# balancing_robot_psoc.net
KiCad netlist of a schematic drawn in EAGLE
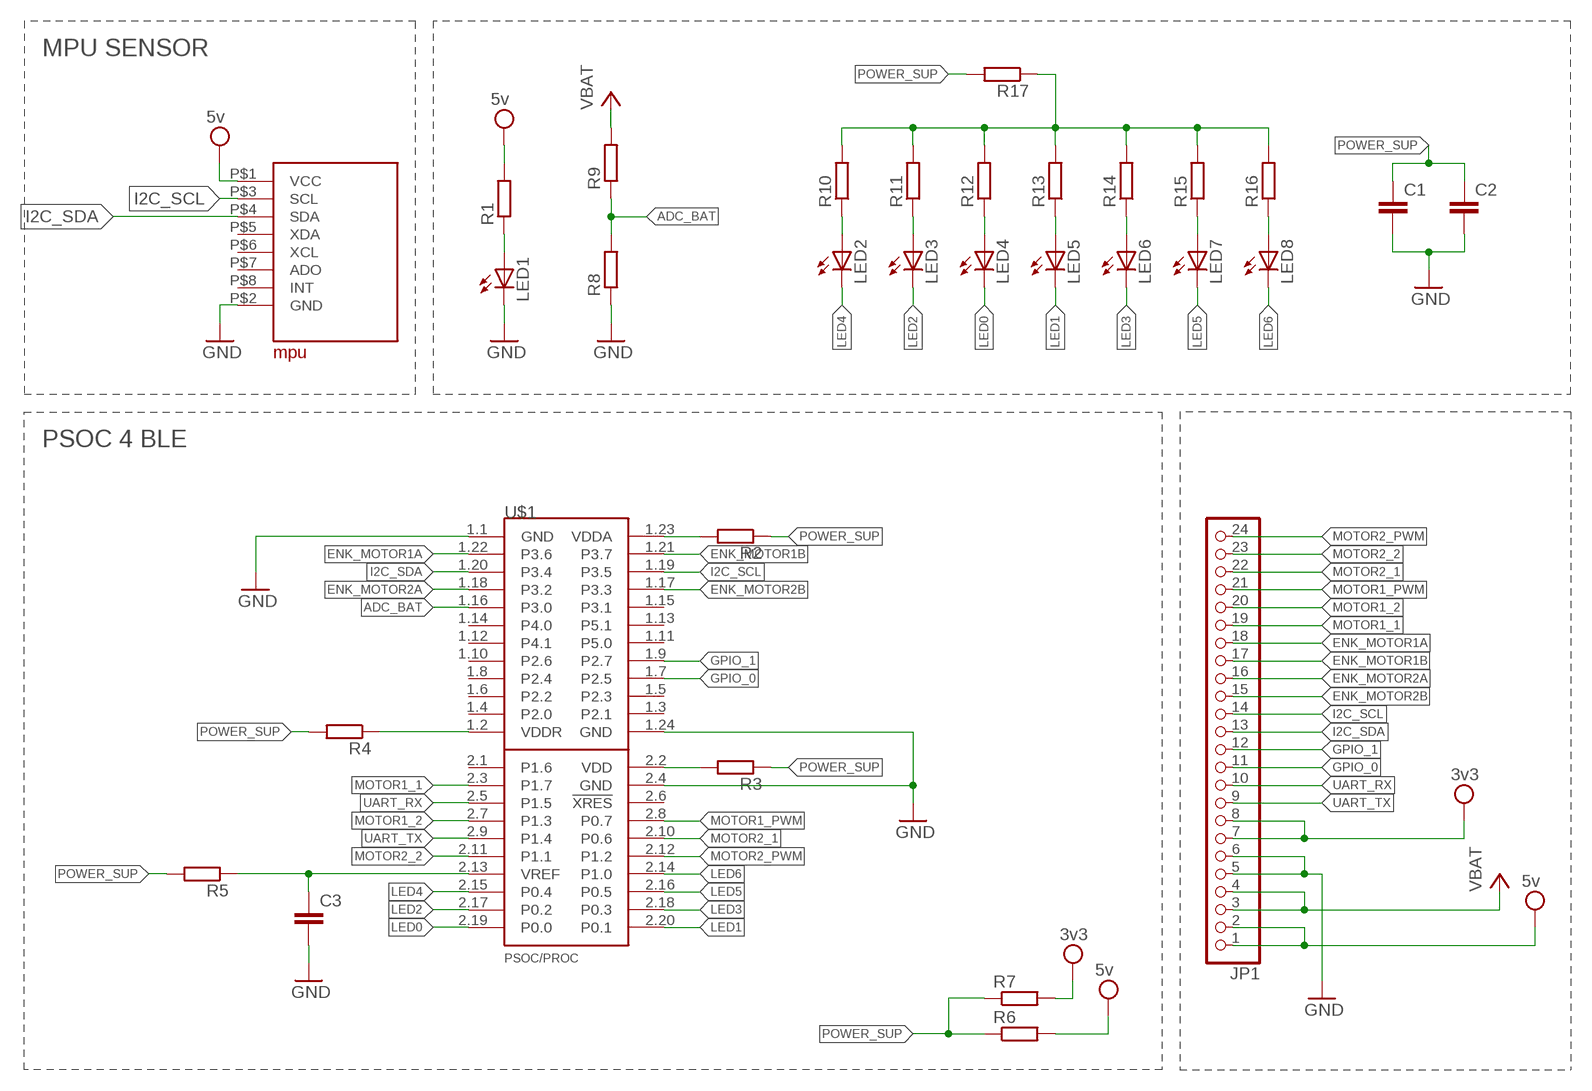
[diagram p0: schematic, sheet 1]

(export (version "E")
  (design (tool "Eeschema 10.0.6"))
  (components
    (comp (ref "C1")
      (value "C-EUC0603")
      (footprint "eagle-import:C0603")
      (libsource (lib "eagle-import") (part "C-EUC0603"))
    )
    (comp (ref "C2")
      (value "C-EUC0805")
      (footprint "eagle-import:C0805")
      (libsource (lib "eagle-import") (part "C-EUC0805"))
    )
    (comp (ref "C3")
      (value "C-EUC0603")
      (footprint "eagle-import:C0603")
      (libsource (lib "eagle-import") (part "C-EUC0603"))
    )
    (comp (ref "JP1")
      (value "PINHD-1X24")
      (footprint "eagle-import:1X24")
      (libsource (lib "eagle-import") (part "PINHD-1X24"))
    )
    (comp (ref "LED1")
      (value "LEDCHIP-LED0603")
      (footprint "eagle-import:CHIP-LED0603")
      (libsource (lib "eagle-import") (part "LEDCHIP-LED0603"))
    )
    (comp (ref "LED2")
      (value "LEDCHIP-LED0603")
      (footprint "eagle-import:CHIP-LED0603")
      (libsource (lib "eagle-import") (part "LEDCHIP-LED0603"))
    )
    (comp (ref "LED3")
      (value "LEDCHIP-LED0603")
      (footprint "eagle-import:CHIP-LED0603")
      (libsource (lib "eagle-import") (part "LEDCHIP-LED0603"))
    )
    (comp (ref "LED4")
      (value "LEDCHIP-LED0603")
      (footprint "eagle-import:CHIP-LED0603")
      (libsource (lib "eagle-import") (part "LEDCHIP-LED0603"))
    )
    (comp (ref "LED5")
      (value "LEDCHIP-LED0603")
      (footprint "eagle-import:CHIP-LED0603")
      (libsource (lib "eagle-import") (part "LEDCHIP-LED0603"))
    )
    (comp (ref "LED6")
      (value "LEDCHIP-LED0603")
      (footprint "eagle-import:CHIP-LED0603")
      (libsource (lib "eagle-import") (part "LEDCHIP-LED0603"))
    )
    (comp (ref "LED7")
      (value "LEDCHIP-LED0603")
      (footprint "eagle-import:CHIP-LED0603")
      (libsource (lib "eagle-import") (part "LEDCHIP-LED0603"))
    )
    (comp (ref "LED8")
      (value "LEDCHIP-LED0603")
      (footprint "eagle-import:CHIP-LED0603")
      (libsource (lib "eagle-import") (part "LEDCHIP-LED0603"))
    )
    (comp (ref "R1")
      (value "R-EU_R0603")
      (footprint "eagle-import:R0603")
      (libsource (lib "eagle-import") (part "R-EU_R0603"))
    )
    (comp (ref "R2")
      (value "R-EU_R0603")
      (footprint "eagle-import:R0603")
      (libsource (lib "eagle-import") (part "R-EU_R0603"))
    )
    (comp (ref "R3")
      (value "R-EU_R0603")
      (footprint "eagle-import:R0603")
      (libsource (lib "eagle-import") (part "R-EU_R0603"))
    )
    (comp (ref "R4")
      (value "R-EU_R0603")
      (footprint "eagle-import:R0603")
      (libsource (lib "eagle-import") (part "R-EU_R0603"))
    )
    (comp (ref "R5")
      (value "R-EU_R0603")
      (footprint "eagle-import:R0603")
      (libsource (lib "eagle-import") (part "R-EU_R0603"))
    )
    (comp (ref "R6")
      (value "R-EU_R0603")
      (footprint "eagle-import:R0603")
      (libsource (lib "eagle-import") (part "R-EU_R0603"))
    )
    (comp (ref "R7")
      (value "R-EU_R0603")
      (footprint "eagle-import:R0603")
      (libsource (lib "eagle-import") (part "R-EU_R0603"))
    )
    (comp (ref "R8")
      (value "R-EU_R0603")
      (footprint "eagle-import:R0603")
      (libsource (lib "eagle-import") (part "R-EU_R0603"))
    )
    (comp (ref "R9")
      (value "R-EU_R0603")
      (footprint "eagle-import:R0603")
      (libsource (lib "eagle-import") (part "R-EU_R0603"))
    )
    (comp (ref "R10")
      (value "R-EU_R0603")
      (footprint "eagle-import:R0603")
      (libsource (lib "eagle-import") (part "R-EU_R0603"))
    )
    (comp (ref "R11")
      (value "R-EU_R0603")
      (footprint "eagle-import:R0603")
      (libsource (lib "eagle-import") (part "R-EU_R0603"))
    )
    (comp (ref "R12")
      (value "R-EU_R0603")
      (footprint "eagle-import:R0603")
      (libsource (lib "eagle-import") (part "R-EU_R0603"))
    )
    (comp (ref "R13")
      (value "R-EU_R0603")
      (footprint "eagle-import:R0603")
      (libsource (lib "eagle-import") (part "R-EU_R0603"))
    )
    (comp (ref "R14")
      (value "R-EU_R0603")
      (footprint "eagle-import:R0603")
      (libsource (lib "eagle-import") (part "R-EU_R0603"))
    )
    (comp (ref "R15")
      (value "R-EU_R0603")
      (footprint "eagle-import:R0603")
      (libsource (lib "eagle-import") (part "R-EU_R0603"))
    )
    (comp (ref "R16")
      (value "R-EU_R0603")
      (footprint "eagle-import:R0603")
      (libsource (lib "eagle-import") (part "R-EU_R0603"))
    )
    (comp (ref "R17")
      (value "R-EU_R0603")
      (footprint "eagle-import:R0603")
      (libsource (lib "eagle-import") (part "R-EU_R0603"))
    )
    (comp (ref "U$1")
      (value "PSOC/PROC")
      (footprint "eagle-import:PSOC_PROC_SOCKET")
      (libsource (lib "eagle-import") (part "PSOC/PROC"))
    )
    (comp (ref "U$5")
      (value "MPU")
      (footprint "eagle-import:MPU")
      (libsource (lib "eagle-import") (part "MPU"))
    )
  )
  (nets
    (net (code "1") (name "3v3") (class "Default")
      (node (ref "JP1") (pin "7") (pinfunction "7_7") (pintype "passive"))
      (node (ref "JP1") (pin "8") (pinfunction "8_8") (pintype "passive"))
      (node (ref "R7") (pin "2") (pinfunction "2_2") (pintype "passive"))
    )
    (net (code "2") (name "5v") (class "Default")
      (node (ref "JP1") (pin "1") (pinfunction "1_1") (pintype "passive"))
      (node (ref "JP1") (pin "2") (pinfunction "2_2") (pintype "passive"))
      (node (ref "R1") (pin "2") (pinfunction "2_2") (pintype "passive"))
      (node (ref "R6") (pin "2") (pinfunction "2_2") (pintype "passive"))
      (node (ref "U$5") (pin "P$1") (pinfunction "VCC_P$1") (pintype "bidirectional"))
    )
    (net (code "3") (name "ADC_BAT") (class "Default")
      (node (ref "R8") (pin "2") (pinfunction "2_2") (pintype "passive"))
      (node (ref "R9") (pin "1") (pinfunction "1_1") (pintype "passive"))
      (node (ref "U$1") (pin "1.16") (pinfunction "P3.0_1.16") (pintype "bidirectional"))
    )
    (net (code "4") (name "ENK_MOTOR1A") (class "Default")
      (node (ref "JP1") (pin "18") (pinfunction "18_18") (pintype "passive"))
      (node (ref "U$1") (pin "1.22") (pinfunction "P3.6_1.22") (pintype "bidirectional"))
    )
    (net (code "5") (name "ENK_MOTOR1B") (class "Default")
      (node (ref "JP1") (pin "17") (pinfunction "17_17") (pintype "passive"))
      (node (ref "U$1") (pin "1.21") (pinfunction "P3.7_1.21") (pintype "bidirectional"))
    )
    (net (code "6") (name "ENK_MOTOR2A") (class "Default")
      (node (ref "JP1") (pin "16") (pinfunction "16_16") (pintype "passive"))
      (node (ref "U$1") (pin "1.18") (pinfunction "P3.2_1.18") (pintype "bidirectional"))
    )
    (net (code "7") (name "ENK_MOTOR2B") (class "Default")
      (node (ref "JP1") (pin "15") (pinfunction "15_15") (pintype "passive"))
      (node (ref "U$1") (pin "1.17") (pinfunction "P3.3_1.17") (pintype "bidirectional"))
    )
    (net (code "8") (name "GND") (class "Default")
      (node (ref "C1") (pin "2") (pinfunction "2_2") (pintype "passive"))
      (node (ref "C2") (pin "2") (pinfunction "2_2") (pintype "passive"))
      (node (ref "C3") (pin "2") (pinfunction "2_2") (pintype "passive"))
      (node (ref "JP1") (pin "5") (pinfunction "5_5") (pintype "passive"))
      (node (ref "JP1") (pin "6") (pinfunction "6_6") (pintype "passive"))
      (node (ref "LED1") (pin "C") (pinfunction "C_C") (pintype "passive"))
      (node (ref "R8") (pin "1") (pinfunction "1_1") (pintype "passive"))
      (node (ref "U$1") (pin "1.1") (pinfunction "GND_1.1") (pintype "bidirectional"))
      (node (ref "U$1") (pin "1.24") (pinfunction "GND_1.24") (pintype "bidirectional"))
      (node (ref "U$1") (pin "2.4") (pinfunction "GND_2.4") (pintype "bidirectional"))
      (node (ref "U$5") (pin "P$2") (pinfunction "GND_P$2") (pintype "bidirectional"))
    )
    (net (code "9") (name "GPIO_0") (class "Default")
      (node (ref "JP1") (pin "11") (pinfunction "11_11") (pintype "passive"))
      (node (ref "U$1") (pin "1.7") (pinfunction "P2.5_1.7") (pintype "bidirectional"))
    )
    (net (code "10") (name "GPIO_1") (class "Default")
      (node (ref "JP1") (pin "12") (pinfunction "12_12") (pintype "passive"))
      (node (ref "U$1") (pin "1.9") (pinfunction "P2.7_1.9") (pintype "bidirectional"))
    )
    (net (code "11") (name "I2C_SCL") (class "Default")
      (node (ref "JP1") (pin "14") (pinfunction "14_14") (pintype "passive"))
      (node (ref "U$1") (pin "1.19") (pinfunction "P3.5_1.19") (pintype "bidirectional"))
      (node (ref "U$5") (pin "P$3") (pinfunction "SCL_P$3") (pintype "bidirectional"))
    )
    (net (code "12") (name "I2C_SDA") (class "Default")
      (node (ref "JP1") (pin "13") (pinfunction "13_13") (pintype "passive"))
      (node (ref "U$1") (pin "1.20") (pinfunction "P3.4_1.20") (pintype "bidirectional"))
      (node (ref "U$5") (pin "P$4") (pinfunction "SDA_P$4") (pintype "bidirectional"))
    )
    (net (code "13") (name "LED0") (class "Default")
      (node (ref "LED4") (pin "C") (pinfunction "C_C") (pintype "passive"))
      (node (ref "U$1") (pin "2.19") (pinfunction "P0.0_2.19") (pintype "bidirectional"))
    )
    (net (code "14") (name "LED1") (class "Default")
      (node (ref "LED5") (pin "C") (pinfunction "C_C") (pintype "passive"))
      (node (ref "U$1") (pin "2.20") (pinfunction "P0.1_2.20") (pintype "bidirectional"))
    )
    (net (code "15") (name "LED2") (class "Default")
      (node (ref "LED3") (pin "C") (pinfunction "C_C") (pintype "passive"))
      (node (ref "U$1") (pin "2.17") (pinfunction "P0.2_2.17") (pintype "bidirectional"))
    )
    (net (code "16") (name "LED3") (class "Default")
      (node (ref "LED6") (pin "C") (pinfunction "C_C") (pintype "passive"))
      (node (ref "U$1") (pin "2.18") (pinfunction "P0.3_2.18") (pintype "bidirectional"))
    )
    (net (code "17") (name "LED4") (class "Default")
      (node (ref "LED2") (pin "C") (pinfunction "C_C") (pintype "passive"))
      (node (ref "U$1") (pin "2.15") (pinfunction "P0.4_2.15") (pintype "bidirectional"))
    )
    (net (code "18") (name "LED5") (class "Default")
      (node (ref "LED7") (pin "C") (pinfunction "C_C") (pintype "passive"))
      (node (ref "U$1") (pin "2.16") (pinfunction "P0.5_2.16") (pintype "bidirectional"))
    )
    (net (code "19") (name "LED6") (class "Default")
      (node (ref "LED8") (pin "C") (pinfunction "C_C") (pintype "passive"))
      (node (ref "U$1") (pin "2.14") (pinfunction "P1.0_2.14") (pintype "bidirectional"))
    )
    (net (code "20") (name "MOTOR1_1") (class "Default")
      (node (ref "JP1") (pin "19") (pinfunction "19_19") (pintype "passive"))
      (node (ref "U$1") (pin "2.3") (pinfunction "P1.7_2.3") (pintype "bidirectional"))
    )
    (net (code "21") (name "MOTOR1_2") (class "Default")
      (node (ref "JP1") (pin "20") (pinfunction "20_20") (pintype "passive"))
      (node (ref "U$1") (pin "2.7") (pinfunction "P1.3_2.7") (pintype "bidirectional"))
    )
    (net (code "22") (name "MOTOR1_PWM") (class "Default")
      (node (ref "JP1") (pin "21") (pinfunction "21_21") (pintype "passive"))
      (node (ref "U$1") (pin "2.8") (pinfunction "P0.7_2.8") (pintype "bidirectional"))
    )
    (net (code "23") (name "MOTOR2_1") (class "Default")
      (node (ref "JP1") (pin "22") (pinfunction "22_22") (pintype "passive"))
      (node (ref "U$1") (pin "2.10") (pinfunction "P0.6_2.10") (pintype "bidirectional"))
    )
    (net (code "24") (name "MOTOR2_2") (class "Default")
      (node (ref "JP1") (pin "23") (pinfunction "23_23") (pintype "passive"))
      (node (ref "U$1") (pin "2.11") (pinfunction "P1.1_2.11") (pintype "bidirectional"))
    )
    (net (code "25") (name "MOTOR2_PWM") (class "Default")
      (node (ref "JP1") (pin "24") (pinfunction "24_24") (pintype "passive"))
      (node (ref "U$1") (pin "2.12") (pinfunction "P1.2_2.12") (pintype "bidirectional"))
    )
    (net (code "26") (name "Net-(LED1-PadA)") (class "Default")
      (node (ref "LED1") (pin "A") (pinfunction "A_A") (pintype "passive"))
      (node (ref "R1") (pin "1") (pinfunction "1_1") (pintype "passive"))
    )
    (net (code "27") (name "Net-(LED2-PadA)") (class "Default")
      (node (ref "LED2") (pin "A") (pinfunction "A_A") (pintype "passive"))
      (node (ref "R10") (pin "1") (pinfunction "1_1") (pintype "passive"))
    )
    (net (code "28") (name "Net-(LED3-PadA)") (class "Default")
      (node (ref "LED3") (pin "A") (pinfunction "A_A") (pintype "passive"))
      (node (ref "R11") (pin "1") (pinfunction "1_1") (pintype "passive"))
    )
    (net (code "29") (name "Net-(LED4-PadA)") (class "Default")
      (node (ref "LED4") (pin "A") (pinfunction "A_A") (pintype "passive"))
      (node (ref "R12") (pin "1") (pinfunction "1_1") (pintype "passive"))
    )
    (net (code "30") (name "Net-(LED5-PadA)") (class "Default")
      (node (ref "LED5") (pin "A") (pinfunction "A_A") (pintype "passive"))
      (node (ref "R13") (pin "1") (pinfunction "1_1") (pintype "passive"))
    )
    (net (code "31") (name "Net-(LED6-PadA)") (class "Default")
      (node (ref "LED6") (pin "A") (pinfunction "A_A") (pintype "passive"))
      (node (ref "R14") (pin "1") (pinfunction "1_1") (pintype "passive"))
    )
    (net (code "32") (name "Net-(LED7-PadA)") (class "Default")
      (node (ref "LED7") (pin "A") (pinfunction "A_A") (pintype "passive"))
      (node (ref "R15") (pin "1") (pinfunction "1_1") (pintype "passive"))
    )
    (net (code "33") (name "Net-(LED8-PadA)") (class "Default")
      (node (ref "LED8") (pin "A") (pinfunction "A_A") (pintype "passive"))
      (node (ref "R16") (pin "1") (pinfunction "1_1") (pintype "passive"))
    )
    (net (code "34") (name "Net-(R10-Pad2)") (class "Default")
      (node (ref "R10") (pin "2") (pinfunction "2_2") (pintype "passive"))
      (node (ref "R11") (pin "2") (pinfunction "2_2") (pintype "passive"))
      (node (ref "R12") (pin "2") (pinfunction "2_2") (pintype "passive"))
      (node (ref "R13") (pin "2") (pinfunction "2_2") (pintype "passive"))
      (node (ref "R14") (pin "2") (pinfunction "2_2") (pintype "passive"))
      (node (ref "R15") (pin "2") (pinfunction "2_2") (pintype "passive"))
      (node (ref "R16") (pin "2") (pinfunction "2_2") (pintype "passive"))
      (node (ref "R17") (pin "1") (pinfunction "1_1") (pintype "passive"))
    )
    (net (code "35") (name "Net-(U$1-VDD)") (class "Default")
      (node (ref "R3") (pin "2") (pinfunction "2_2") (pintype "passive"))
      (node (ref "U$1") (pin "2.2") (pinfunction "VDD_2.2") (pintype "bidirectional"))
    )
    (net (code "36") (name "Net-(U$1-VDDA)") (class "Default")
      (node (ref "R2") (pin "2") (pinfunction "2_2") (pintype "passive"))
      (node (ref "U$1") (pin "1.23") (pinfunction "VDDA_1.23") (pintype "bidirectional"))
    )
    (net (code "37") (name "Net-(U$1-VDDR)") (class "Default")
      (node (ref "R4") (pin "1") (pinfunction "1_1") (pintype "passive"))
      (node (ref "U$1") (pin "1.2") (pinfunction "VDDR_1.2") (pintype "bidirectional"))
    )
    (net (code "38") (name "Net-(U$1-VREF)") (class "Default")
      (node (ref "C3") (pin "1") (pinfunction "1_1") (pintype "passive"))
      (node (ref "R5") (pin "1") (pinfunction "1_1") (pintype "passive"))
      (node (ref "U$1") (pin "2.13") (pinfunction "VREF_2.13") (pintype "bidirectional"))
    )
    (net (code "39") (name "POWER_SUP") (class "Default")
      (node (ref "C1") (pin "1") (pinfunction "1_1") (pintype "passive"))
      (node (ref "C2") (pin "1") (pinfunction "1_1") (pintype "passive"))
      (node (ref "R17") (pin "2") (pinfunction "2_2") (pintype "passive"))
      (node (ref "R2") (pin "1") (pinfunction "1_1") (pintype "passive"))
      (node (ref "R3") (pin "1") (pinfunction "1_1") (pintype "passive"))
      (node (ref "R4") (pin "2") (pinfunction "2_2") (pintype "passive"))
      (node (ref "R5") (pin "2") (pinfunction "2_2") (pintype "passive"))
      (node (ref "R6") (pin "1") (pinfunction "1_1") (pintype "passive"))
      (node (ref "R7") (pin "1") (pinfunction "1_1") (pintype "passive"))
    )
    (net (code "40") (name "UART_RX") (class "Default")
      (node (ref "JP1") (pin "10") (pinfunction "10_10") (pintype "passive"))
      (node (ref "U$1") (pin "2.5") (pinfunction "P1.5_2.5") (pintype "bidirectional"))
    )
    (net (code "41") (name "UART_TX") (class "Default")
      (node (ref "JP1") (pin "9") (pinfunction "9_9") (pintype "passive"))
      (node (ref "U$1") (pin "2.9") (pinfunction "P1.4_2.9") (pintype "bidirectional"))
    )
    (net (code "42") (name "VBAT") (class "Default")
      (node (ref "JP1") (pin "3") (pinfunction "3_3") (pintype "passive"))
      (node (ref "JP1") (pin "4") (pinfunction "4_4") (pintype "passive"))
      (node (ref "R9") (pin "2") (pinfunction "2_2") (pintype "passive"))
    )
    (net (code "43") (name "unconnected-(U$1-P1.6-Pad2.1)") (class "Default")
      (node (ref "U$1") (pin "2.1") (pinfunction "P1.6_2.1") (pintype "bidirectional"))
    )
    (net (code "44") (name "unconnected-(U$1-P2.0-Pad1.4)") (class "Default")
      (node (ref "U$1") (pin "1.4") (pinfunction "P2.0_1.4") (pintype "bidirectional"))
    )
    (net (code "45") (name "unconnected-(U$1-P2.1-Pad1.3)") (class "Default")
      (node (ref "U$1") (pin "1.3") (pinfunction "P2.1_1.3") (pintype "bidirectional"))
    )
    (net (code "46") (name "unconnected-(U$1-P2.2-Pad1.6)") (class "Default")
      (node (ref "U$1") (pin "1.6") (pinfunction "P2.2_1.6") (pintype "bidirectional"))
    )
    (net (code "47") (name "unconnected-(U$1-P2.3-Pad1.5)") (class "Default")
      (node (ref "U$1") (pin "1.5") (pinfunction "P2.3_1.5") (pintype "bidirectional"))
    )
    (net (code "48") (name "unconnected-(U$1-P2.4-Pad1.8)") (class "Default")
      (node (ref "U$1") (pin "1.8") (pinfunction "P2.4_1.8") (pintype "bidirectional"))
    )
    (net (code "49") (name "unconnected-(U$1-P2.6-Pad1.10)") (class "Default")
      (node (ref "U$1") (pin "1.10") (pinfunction "P2.6_1.10") (pintype "bidirectional"))
    )
    (net (code "50") (name "unconnected-(U$1-P3.1-Pad1.15)") (class "Default")
      (node (ref "U$1") (pin "1.15") (pinfunction "P3.1_1.15") (pintype "bidirectional"))
    )
    (net (code "51") (name "unconnected-(U$1-P4.0-Pad1.14)") (class "Default")
      (node (ref "U$1") (pin "1.14") (pinfunction "P4.0_1.14") (pintype "bidirectional"))
    )
    (net (code "52") (name "unconnected-(U$1-P4.1-Pad1.12)") (class "Default")
      (node (ref "U$1") (pin "1.12") (pinfunction "P4.1_1.12") (pintype "bidirectional"))
    )
    (net (code "53") (name "unconnected-(U$1-P5.0-Pad1.11)") (class "Default")
      (node (ref "U$1") (pin "1.11") (pinfunction "P5.0_1.11") (pintype "bidirectional"))
    )
    (net (code "54") (name "unconnected-(U$1-P5.1-Pad1.13)") (class "Default")
      (node (ref "U$1") (pin "1.13") (pinfunction "P5.1_1.13") (pintype "bidirectional"))
    )
    (net (code "55") (name "unconnected-(U$1-~{XRES}-Pad2.6)") (class "Default")
      (node (ref "U$1") (pin "2.6") (pinfunction "~{XRES}_2.6") (pintype "bidirectional"))
    )
    (net (code "56") (name "unconnected-(U$5-ADO-PadP$7)") (class "Default")
      (node (ref "U$5") (pin "P$7") (pinfunction "ADO_P$7") (pintype "bidirectional"))
    )
    (net (code "57") (name "unconnected-(U$5-INT-PadP$8)") (class "Default")
      (node (ref "U$5") (pin "P$8") (pinfunction "INT_P$8") (pintype "bidirectional"))
    )
    (net (code "58") (name "unconnected-(U$5-XCL-PadP$6)") (class "Default")
      (node (ref "U$5") (pin "P$6") (pinfunction "XCL_P$6") (pintype "bidirectional"))
    )
    (net (code "59") (name "unconnected-(U$5-XDA-PadP$5)") (class "Default")
      (node (ref "U$5") (pin "P$5") (pinfunction "XDA_P$5") (pintype "bidirectional"))
    )
  )
)
